# Tactile_SW.net
KiCad netlist of a schematic drawn in Altium Designer
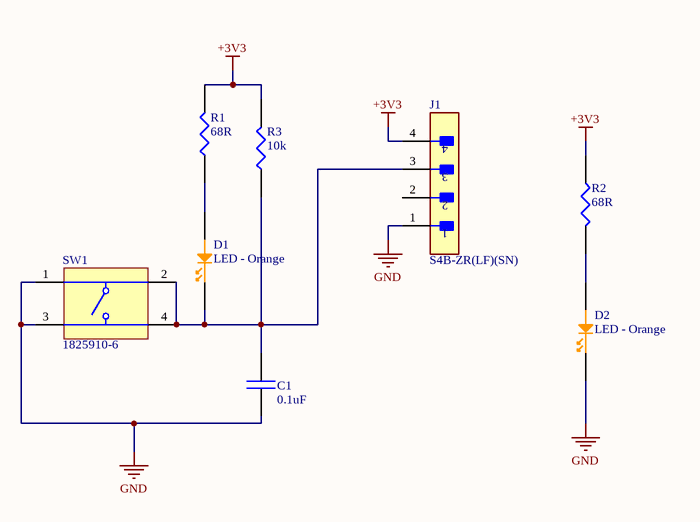
[diagram p0: Tactile_SW.SchDoc]

(export (version "E")
  (design (tool "Eeschema 10.0.6"))
  (components
    (comp (ref "C1")
      (value "0.1uF")
      (footprint "0.1uF 0603")
      (description "CAP CER 0.1UF 16V X7R 0603")
      (fields
        (field (name "MANUFACTURER") "KEMET")
        (field (name "MANUFACTURER PART NUMBER") "C0603C104M4RACTU")
      )
      (libsource (lib "Limit_Switch") (part "C0603C104M4RACTU"))
    )
    (comp (ref "D1")
      (value "LED - Orange")
      (footprint "LED0603-Orange")
      (description "LED ORANGE CLEAR SMD")
      (fields
        (field (name "MANUFACTURER") "Vishay Lite-On")
        (field (name "MANUFACTURER PART NUMBER") "LTST-C191KFKT")
      )
      (libsource (lib "Limit_Switch") (part "LTST-C191KFKT"))
    )
    (comp (ref "D2")
      (value "LED - Orange")
      (footprint "LED0603-Orange")
      (description "LED ORANGE CLEAR SMD")
      (fields
        (field (name "MANUFACTURER") "Vishay Lite-On")
        (field (name "MANUFACTURER PART NUMBER") "LTST-C191KFKT")
      )
      (libsource (lib "Limit_Switch") (part "LTST-C191KFKT"))
    )
    (comp (ref "J1")
      (value "S4B-ZR(LF)(SN)")
      (footprint "FP-S4B-ZR_LF_SN-MFG")
      (description "CONN HEADER R/A 4POS 1.5MM")
      (fields
        (field (name "OCTOPART") "https://octopart.com/s4b-zr%28lf%29%28sn%29-jst-248835")
        (field (name "MANUFACTURER") "JST")
      )
      (libsource (lib "Altium Content Vault") (part "299a8cea1bdcbc3624fe62c390fa72c"))
    )
    (comp (ref "R1")
      (value "68R")
      (footprint "68R 0603")
      (description "CRGP 0603 68R 1%")
      (fields
        (field (name "MANUFACTURER") "TE Connectivity")
        (field (name "MANUFACTURER PART NUMBER") "CRGP0603F68R")
      )
      (libsource (lib "Limit_Switch") (part "CRGP0603F68R"))
    )
    (comp (ref "R2")
      (value "68R")
      (footprint "68R 0603")
      (description "CRGP 0603 68R 1%")
      (fields
        (field (name "MANUFACTURER") "TE Connectivity")
        (field (name "MANUFACTURER PART NUMBER") "CRGP0603F68R")
      )
      (libsource (lib "Limit_Switch") (part "CRGP0603F68R"))
    )
    (comp (ref "R3")
      (value "10k")
      (footprint "10k R0603")
      (description "RES 10.0K OHM 1/10W 1% 0603")
      (fields
        (field (name "MANUFACTURER") "TE Connectivity")
        (field (name "MANUFACTURER PART NUMBER") "CRG0603F10K/10")
      )
      (libsource (lib "Limit_Switch") (part "CRG0603F10K/10"))
    )
    (comp (ref "SW1")
      (value "1825910-6")
      (footprint "TECO-1825910-6_V")
      (description "Tact Switch, SPST-NO, 0.05 A, -35 to 85 degC, 4-Pin THD, RoHS, Bulk")
      (fields (field (name "MANUFACTURER") "TE Connectivity"))
      (libsource (lib "Altium Content Vault") (part "SW-SPST-4_A"))
    )
  )
  (nets
    (net (code "1") (name "+3V3") (class "Default")
      (node (ref "J1") (pin "4") (pinfunction "4_4") (pintype "passive"))
      (node (ref "R1") (pin "2") (pinfunction "2_2") (pintype "passive"))
      (node (ref "R2") (pin "1") (pinfunction "1_1") (pintype "passive"))
      (node (ref "R3") (pin "2") (pinfunction "2_2") (pintype "passive"))
    )
    (net (code "2") (name "GND") (class "Default")
      (node (ref "C1") (pin "1") (pinfunction "1_1") (pintype "passive"))
      (node (ref "D2") (pin "1") (pinfunction "Cathode_1") (pintype "passive"))
      (node (ref "J1") (pin "1") (pinfunction "1_1") (pintype "passive"))
      (node (ref "SW1") (pin "1") (pinfunction "1_1") (pintype "passive"))
      (node (ref "SW1") (pin "3") (pinfunction "3_3") (pintype "passive"))
    )
    (net (code "3") (name "Net-(D1-Anode)") (class "Default")
      (node (ref "D1") (pin "2") (pinfunction "Anode_2") (pintype "passive"))
      (node (ref "R1") (pin "1") (pinfunction "1_1") (pintype "passive"))
    )
    (net (code "4") (name "Net-(D1-Cathode)") (class "Default")
      (node (ref "C1") (pin "2") (pinfunction "2_2") (pintype "passive"))
      (node (ref "D1") (pin "1") (pinfunction "Cathode_1") (pintype "passive"))
      (node (ref "J1") (pin "3") (pinfunction "3_3") (pintype "passive"))
      (node (ref "R3") (pin "1") (pinfunction "1_1") (pintype "passive"))
      (node (ref "SW1") (pin "2") (pinfunction "2_2") (pintype "passive"))
      (node (ref "SW1") (pin "4") (pinfunction "4_4") (pintype "passive"))
    )
    (net (code "5") (name "Net-(D2-Anode)") (class "Default")
      (node (ref "D2") (pin "2") (pinfunction "Anode_2") (pintype "passive"))
      (node (ref "R2") (pin "2") (pinfunction "2_2") (pintype "passive"))
    )
    (net (code "6") (name "unconnected-(J1-Pad2)") (class "Default")
      (node (ref "J1") (pin "2") (pinfunction "2_2") (pintype "passive"))
    )
  )
)
